# Vanta-Black_v2.net
KiCad netlist of a schematic drawn in EAGLE
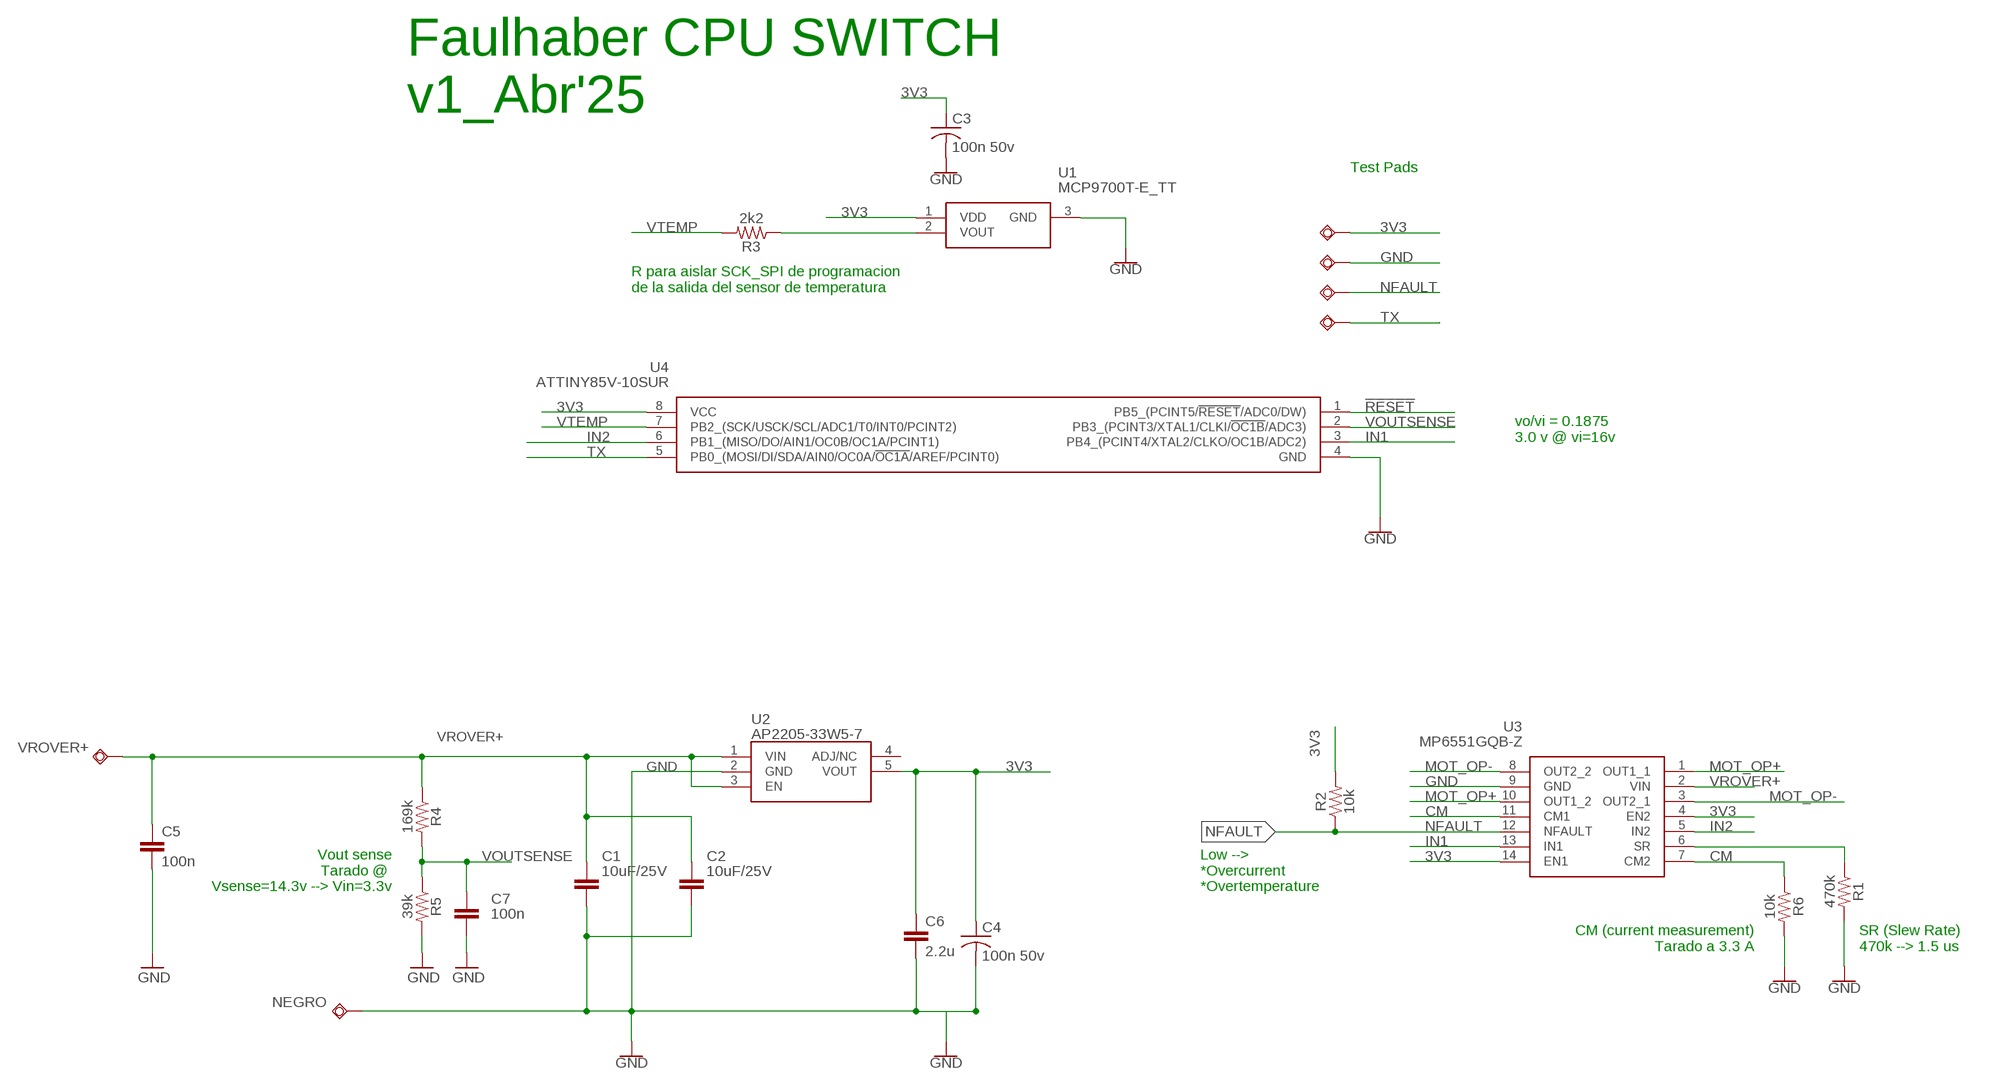
[diagram p0: schematic, sheet 1]

(export (version "E")
  (design (tool "Eeschema 10.0.6"))
  (components
    (comp (ref "3V3")
      (value "TESTPAD_TPSQB1,27")
      (footprint "eagle-import:TESTPAD_B1,27")
      (libsource (lib "eagle-import") (part "TESTPAD_TPSQB1,27"))
    )
    (comp (ref "C1")
      (value "10uF/25V")
      (footprint "eagle-import:CAPC2012X110")
      (libsource (lib "eagle-import") (part "CCHIP-0805(2012-METRIC)_"))
    )
    (comp (ref "C2")
      (value "10uF/25V")
      (footprint "eagle-import:CAPC2012X110")
      (libsource (lib "eagle-import") (part "CCHIP-0805(2012-METRIC)_"))
    )
    (comp (ref "C3")
      (value "100n 50v")
      (footprint "eagle-import:C0805")
      (libsource (lib "eagle-import") (part "C-USC0805"))
    )
    (comp (ref "C4")
      (value "100n 50v")
      (footprint "eagle-import:C0805")
      (libsource (lib "eagle-import") (part "C-USC0805"))
    )
    (comp (ref "C5")
      (value "100n")
      (footprint "eagle-import:0603-CAP")
      (libsource (lib "eagle-import") (part "4.7UF-6.3V-10%(0603)0603"))
    )
    (comp (ref "C6")
      (value "2.2u")
      (footprint "eagle-import:0603-CAP")
      (libsource (lib "eagle-import") (part "4.7UF-6.3V-10%(0603)0603"))
    )
    (comp (ref "C7")
      (value "100n")
      (footprint "eagle-import:0603")
      (libsource (lib "eagle-import") (part "0.1UF-0603-25V-(+80/-20%)"))
    )
    (comp (ref "GND")
      (value "TESTPAD_TPSQB1,27")
      (footprint "eagle-import:TESTPAD_B1,27")
      (libsource (lib "eagle-import") (part "TESTPAD_TPSQB1,27"))
    )
    (comp (ref "NEGRO")
      (value "TESTPAD_TPSQTP10SQ")
      (footprint "eagle-import:TESTPAD_TP10SQ")
      (libsource (lib "eagle-import") (part "BeagleBone_Blue_R3_5828899_TESTPAD_TPSQTP10SQ"))
    )
    (comp (ref "R1")
      (value "470k")
      (footprint "eagle-import:0603")
      (libsource (lib "eagle-import") (part "RESISTOR0603"))
    )
    (comp (ref "R2")
      (value "10k")
      (footprint "eagle-import:0603")
      (libsource (lib "eagle-import") (part "RESISTOR0603"))
    )
    (comp (ref "R3")
      (value "2k2")
      (footprint "eagle-import:0603")
      (libsource (lib "eagle-import") (part "RESISTOR0603"))
    )
    (comp (ref "R4")
      (value "169k")
      (footprint "eagle-import:0603")
      (libsource (lib "eagle-import") (part "RESISTOR0603"))
    )
    (comp (ref "R5")
      (value "39k")
      (footprint "eagle-import:0603")
      (libsource (lib "eagle-import") (part "RESISTOR0603"))
    )
    (comp (ref "R6")
      (value "10k")
      (footprint "eagle-import:0603")
      (libsource (lib "eagle-import") (part "RESISTOR0603"))
    )
    (comp (ref "U1")
      (value "MCP9700T-E_TT")
      (footprint "eagle-import:SOT95P237X112-3N")
      (fields
        (field (name "ARROW_PART_NUMBER") "MCP9700T-E/TT")
        (field (name "MOUSER_PART_NUMBER") "579-MCP9700T-E/TT")
      )
      (libsource (lib "eagle-import") (part "MCP9700T-E_TT"))
    )
    (comp (ref "U2")
      (value "AP2205-33W5-7")
      (footprint "eagle-import:SOT95P282X145-5N")
      (fields
        (field (name "MANUFACTURER_PART_NUMBER") "AP2205-W5-7")
        (field (name "MOUSER_PART_NUMBER") "621-AP2205-W5-7")
      )
      (libsource (lib "eagle-import") (part "AP2205-W5-7"))
    )
    (comp (ref "U3")
      (value "MP6551GQB-Z")
      (footprint "eagle-import:MP6551GQBZ")
      (fields (field (name "MOUSER_PART_NUMBER") "946-MP6551GQB-Z"))
      (libsource (lib "eagle-import") (part "MP6551GQB-Z"))
    )
    (comp (ref "U4")
      (value "ATTINY85V-10SUR")
      (footprint "eagle-import:SOIC127P798X216-8N")
      (fields (field (name "FARNELL2_PART_NUMBER") "2851618RL"))
      (libsource (lib "eagle-import") (part "ATTINY85V-10SUR"))
    )
    (comp (ref "USB+")
      (value "TESTPAD_TPSQB1,27")
      (footprint "eagle-import:TESTPAD_B1,27")
      (libsource (lib "eagle-import") (part "TESTPAD_TPSQB1,27"))
    )
    (comp (ref "USB-")
      (value "TESTPAD_TPSQB1,27")
      (footprint "eagle-import:TESTPAD_B1,27")
      (libsource (lib "eagle-import") (part "TESTPAD_TPSQB1,27"))
    )
    (comp (ref "VROVER+")
      (value "TESTPAD_TPSQTP10SQ")
      (footprint "eagle-import:TESTPAD_TP10SQ")
      (libsource (lib "eagle-import") (part "BeagleBone_Blue_R3_5828899_TESTPAD_TPSQTP10SQ"))
    )
  )
  (nets
    (net (code "1") (name "/3V3") (class "Default")
      (node (ref "3V3") (pin "TP") (pinfunction "TP_TP") (pintype "input"))
      (node (ref "C3") (pin "1") (pinfunction "1_1") (pintype "passive"))
      (node (ref "C4") (pin "1") (pinfunction "1_1") (pintype "passive"))
      (node (ref "C6") (pin "1") (pinfunction "1_1") (pintype "passive"))
      (node (ref "R2") (pin "2") (pinfunction "2_2") (pintype "passive"))
      (node (ref "U1") (pin "1") (pinfunction "VDD_1") (pintype "bidirectional"))
      (node (ref "U2") (pin "5") (pinfunction "VOUT_5") (pintype "bidirectional"))
      (node (ref "U3") (pin "14") (pinfunction "EN1_14") (pintype "bidirectional"))
      (node (ref "U3") (pin "4") (pinfunction "EN2_4") (pintype "bidirectional"))
      (node (ref "U4") (pin "8") (pinfunction "VCC_8") (pintype "bidirectional"))
    )
    (net (code "2") (name "/CM") (class "Default")
      (node (ref "R6") (pin "1") (pinfunction "1_1") (pintype "passive"))
      (node (ref "U3") (pin "11") (pinfunction "CM1_11") (pintype "bidirectional"))
      (node (ref "U3") (pin "7") (pinfunction "CM2_7") (pintype "bidirectional"))
    )
    (net (code "3") (name "/IN1") (class "Default")
      (node (ref "U3") (pin "13") (pinfunction "IN1_13") (pintype "bidirectional"))
      (node (ref "U4") (pin "3") (pinfunction "PB4_(PCINT4/XTAL2/CLKO/OC1B/ADC2)_3") (pintype "bidirectional"))
    )
    (net (code "4") (name "/IN2") (class "Default")
      (node (ref "U3") (pin "5") (pinfunction "IN2_5") (pintype "bidirectional"))
      (node (ref "U4") (pin "6") (pinfunction "PB1_(MISO/DO/AIN1/OC0B/OC1A/PCINT1)_6") (pintype "bidirectional"))
    )
    (net (code "5") (name "/MOT_OP+") (class "Default")
      (node (ref "U3") (pin "1") (pinfunction "OUT1_1_1") (pintype "bidirectional"))
      (node (ref "U3") (pin "10") (pinfunction "OUT1_2_10") (pintype "bidirectional"))
    )
    (net (code "6") (name "/MOT_OP-") (class "Default")
      (node (ref "U3") (pin "3") (pinfunction "OUT2_1_3") (pintype "bidirectional"))
      (node (ref "U3") (pin "8") (pinfunction "OUT2_2_8") (pintype "bidirectional"))
    )
    (net (code "7") (name "/TX") (class "Default")
      (node (ref "U4") (pin "5") (pinfunction "PB0_(MOSI/DI/SDA/AIN0/OC0A/~{OC1A}/AREF/PCINT0)_5") (pintype "bidirectional"))
      (node (ref "USB-") (pin "TP") (pinfunction "TP_TP") (pintype "input"))
    )
    (net (code "8") (name "/VOUTSENSE") (class "Default")
      (node (ref "C7") (pin "1") (pinfunction "1_1") (pintype "passive"))
      (node (ref "R4") (pin "2") (pinfunction "2_2") (pintype "passive"))
      (node (ref "R5") (pin "1") (pinfunction "1_1") (pintype "passive"))
      (node (ref "U4") (pin "2") (pinfunction "PB3_(PCINT3/XTAL1/CLKI/~{OC1B}/ADC3)_2") (pintype "bidirectional"))
    )
    (net (code "9") (name "/VROVER+") (class "Default")
      (node (ref "C1") (pin "1") (pinfunction "1_1") (pintype "passive"))
      (node (ref "C2") (pin "1") (pinfunction "1_1") (pintype "passive"))
      (node (ref "C5") (pin "1") (pinfunction "1_1") (pintype "passive"))
      (node (ref "R4") (pin "1") (pinfunction "1_1") (pintype "passive"))
      (node (ref "U2") (pin "1") (pinfunction "VIN_1") (pintype "bidirectional"))
      (node (ref "U2") (pin "3") (pinfunction "EN_3") (pintype "bidirectional"))
      (node (ref "U3") (pin "2") (pinfunction "VIN_2") (pintype "bidirectional"))
      (node (ref "VROVER+") (pin "TP") (pinfunction "TP_TP") (pintype "input"))
    )
    (net (code "10") (name "/VTEMP") (class "Default")
      (node (ref "R3") (pin "2") (pinfunction "2_2") (pintype "passive"))
      (node (ref "U4") (pin "7") (pinfunction "PB2_(SCK/USCK/SCL/ADC1/T0/INT0/PCINT2)_7") (pintype "bidirectional"))
    )
    (net (code "11") (name "/~{RESET}") (class "Default")
      (node (ref "U4") (pin "1") (pinfunction "PB5_(PCINT5/~{RESET}/ADC0/DW)_1") (pintype "bidirectional"))
    )
    (net (code "12") (name "GND") (class "Default")
      (node (ref "C1") (pin "2") (pinfunction "2_2") (pintype "passive"))
      (node (ref "C2") (pin "2") (pinfunction "2_2") (pintype "passive"))
      (node (ref "C3") (pin "2") (pinfunction "2_2") (pintype "passive"))
      (node (ref "C4") (pin "2") (pinfunction "2_2") (pintype "passive"))
      (node (ref "C5") (pin "2") (pinfunction "2_2") (pintype "passive"))
      (node (ref "C6") (pin "2") (pinfunction "2_2") (pintype "passive"))
      (node (ref "C7") (pin "2") (pinfunction "2_2") (pintype "passive"))
      (node (ref "GND") (pin "TP") (pinfunction "TP_TP") (pintype "input"))
      (node (ref "NEGRO") (pin "TP") (pinfunction "TP_TP") (pintype "input"))
      (node (ref "R1") (pin "2") (pinfunction "2_2") (pintype "passive"))
      (node (ref "R5") (pin "2") (pinfunction "2_2") (pintype "passive"))
      (node (ref "R6") (pin "2") (pinfunction "2_2") (pintype "passive"))
      (node (ref "U1") (pin "3") (pinfunction "GND_3") (pintype "bidirectional"))
      (node (ref "U2") (pin "2") (pinfunction "GND_2") (pintype "bidirectional"))
      (node (ref "U3") (pin "9") (pinfunction "GND_9") (pintype "bidirectional"))
      (node (ref "U4") (pin "4") (pinfunction "GND_4") (pintype "bidirectional"))
    )
    (net (code "13") (name "NFAULT") (class "Default")
      (node (ref "R2") (pin "1") (pinfunction "1_1") (pintype "passive"))
      (node (ref "U3") (pin "12") (pinfunction "NFAULT_12") (pintype "bidirectional"))
      (node (ref "USB+") (pin "TP") (pinfunction "TP_TP") (pintype "input"))
    )
    (net (code "14") (name "Net-(U1-VOUT)") (class "Default")
      (node (ref "R3") (pin "1") (pinfunction "1_1") (pintype "passive"))
      (node (ref "U1") (pin "2") (pinfunction "VOUT_2") (pintype "bidirectional"))
    )
    (net (code "15") (name "Net-(U3-SR)") (class "Default")
      (node (ref "R1") (pin "1") (pinfunction "1_1") (pintype "passive"))
      (node (ref "U3") (pin "6") (pinfunction "SR_6") (pintype "bidirectional"))
    )
    (net (code "16") (name "unconnected-(U2-ADJ{slash}NC-Pad4)") (class "Default")
      (node (ref "U2") (pin "4") (pinfunction "ADJ/NC_4") (pintype "bidirectional"))
    )
  )
)
